# pomodoro.net
KiCad netlist of a schematic drawn in EAGLE
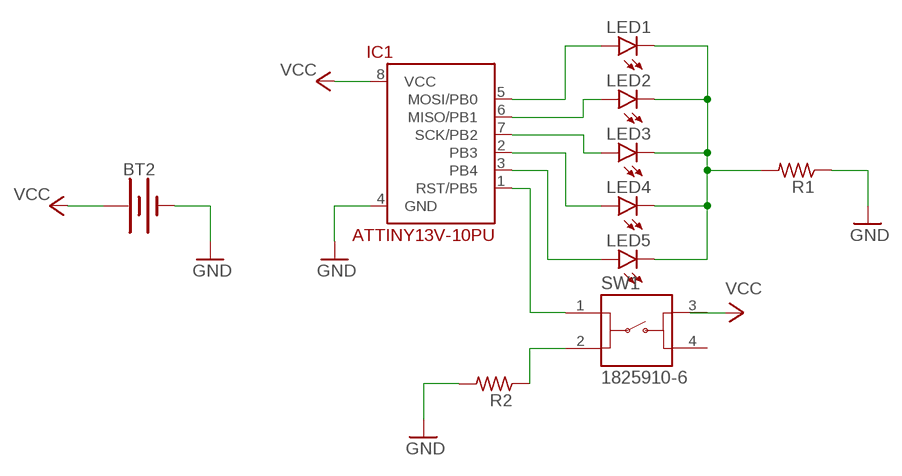
[diagram p0: schematic, sheet 1]

(export (version "E")
  (design (tool "Eeschema 10.0.6"))
  (components
    (comp (ref "BT2")
      (value "BATTERY-20MM_PTH_KIT")
      (footprint "eagle-import:BATTCOM_20MM_PTH_KIT")
      (libsource (lib "eagle-import") (part "BATTERY-20MM_PTH_KIT"))
    )
    (comp (ref "IC1")
      (value "ATTINY13V-10PU")
      (footprint "eagle-import:DIL08")
      (libsource (lib "eagle-import") (part "ATTINY13V-10PU"))
    )
    (comp (ref "LED1")
      (value "LED3MM")
      (footprint "eagle-import:LED3MM")
      (libsource (lib "eagle-import") (part "LED3MM"))
    )
    (comp (ref "LED2")
      (value "LED3MM")
      (footprint "eagle-import:LED3MM")
      (libsource (lib "eagle-import") (part "LED3MM"))
    )
    (comp (ref "LED3")
      (value "LED3MM")
      (footprint "eagle-import:LED3MM")
      (libsource (lib "eagle-import") (part "LED3MM"))
    )
    (comp (ref "LED4")
      (value "LED3MM")
      (footprint "eagle-import:LED3MM")
      (libsource (lib "eagle-import") (part "LED3MM"))
    )
    (comp (ref "LED5")
      (value "LED3MM")
      (footprint "eagle-import:LED3MM")
      (libsource (lib "eagle-import") (part "LED3MM"))
    )
    (comp (ref "R1")
      (value "R-US_0204/7")
      (footprint "eagle-import:0204_7")
      (libsource (lib "eagle-import") (part "R-US_0204/7"))
    )
    (comp (ref "R2")
      (value "R-US_0204/7")
      (footprint "eagle-import:0204_7")
      (libsource (lib "eagle-import") (part "R-US_0204/7"))
    )
    (comp (ref "SW1")
      (value "1825910-6")
      (footprint "eagle-import:1825910-6")
      (fields
        (field (name "DIGIKEY_PART_NUMBER") "450-1650-ND")
        (field (name "MANUFACTURER") "TE Connectivity ALCOSWITCH Switches")
        (field (name "CREATED_BY") " PCBLayout.com")
      )
      (libsource (lib "eagle-import") (part "1825910-6"))
    )
  )
  (nets
    (net (code "1") (name "GND") (class "Default")
      (node (ref "BT2") (pin "2") (pinfunction "-_2") (pintype "power_in"))
      (node (ref "IC1") (pin "4") (pinfunction "GND_4") (pintype "power_in"))
      (node (ref "R1") (pin "1") (pinfunction "1_1") (pintype "passive"))
      (node (ref "R2") (pin "2") (pinfunction "2_2") (pintype "passive"))
    )
    (net (code "2") (name "Net-(IC1-MISO{slash}PB1)") (class "Default")
      (node (ref "IC1") (pin "6") (pinfunction "MISO/PB1_6") (pintype "bidirectional"))
      (node (ref "LED2") (pin "A") (pinfunction "A_A") (pintype "passive"))
    )
    (net (code "3") (name "Net-(IC1-MOSI{slash}PB0)") (class "Default")
      (node (ref "IC1") (pin "5") (pinfunction "MOSI/PB0_5") (pintype "bidirectional"))
      (node (ref "LED1") (pin "A") (pinfunction "A_A") (pintype "passive"))
    )
    (net (code "4") (name "Net-(IC1-PB3)") (class "Default")
      (node (ref "IC1") (pin "2") (pinfunction "PB3_2") (pintype "bidirectional"))
      (node (ref "LED4") (pin "A") (pinfunction "A_A") (pintype "passive"))
    )
    (net (code "5") (name "Net-(IC1-PB4)") (class "Default")
      (node (ref "IC1") (pin "3") (pinfunction "PB4_3") (pintype "bidirectional"))
      (node (ref "LED5") (pin "A") (pinfunction "A_A") (pintype "passive"))
    )
    (net (code "6") (name "Net-(IC1-RST{slash}PB5)") (class "Default")
      (node (ref "IC1") (pin "1") (pinfunction "RST/PB5_1") (pintype "bidirectional"))
      (node (ref "SW1") (pin "1") (pinfunction "1_1") (pintype "passive"))
    )
    (net (code "7") (name "Net-(IC1-SCK{slash}PB2)") (class "Default")
      (node (ref "IC1") (pin "7") (pinfunction "SCK/PB2_7") (pintype "bidirectional"))
      (node (ref "LED3") (pin "A") (pinfunction "A_A") (pintype "passive"))
    )
    (net (code "8") (name "Net-(LED1-C)") (class "Default")
      (node (ref "LED1") (pin "K") (pinfunction "C_K") (pintype "passive"))
      (node (ref "LED2") (pin "K") (pinfunction "C_K") (pintype "passive"))
      (node (ref "LED3") (pin "K") (pinfunction "C_K") (pintype "passive"))
      (node (ref "LED4") (pin "K") (pinfunction "C_K") (pintype "passive"))
      (node (ref "LED5") (pin "K") (pinfunction "C_K") (pintype "passive"))
      (node (ref "R1") (pin "2") (pinfunction "2_2") (pintype "passive"))
    )
    (net (code "9") (name "Net-(R2-Pad1)") (class "Default")
      (node (ref "R2") (pin "1") (pinfunction "1_1") (pintype "passive"))
      (node (ref "SW1") (pin "2") (pinfunction "2_2") (pintype "passive"))
    )
    (net (code "10") (name "VCC") (class "Default")
      (node (ref "BT2") (pin "1") (pinfunction "+_1") (pintype "power_in"))
      (node (ref "IC1") (pin "8") (pinfunction "VCC_8") (pintype "power_in"))
      (node (ref "SW1") (pin "3") (pinfunction "3_3") (pintype "passive"))
    )
    (net (code "11") (name "unconnected-(SW1-Pad4)") (class "Default")
      (node (ref "SW1") (pin "4") (pinfunction "4_4") (pintype "passive"))
    )
  )
)
